# GNNS_SAM-M10Q-00B.net
KiCad netlist of a schematic drawn in Altium Designer
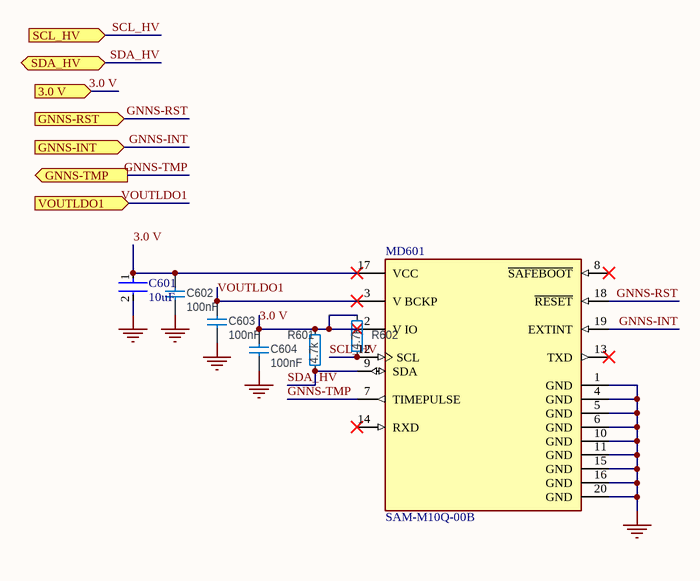
[diagram p0: GNNS (SAM-M10Q-00B).SchDoc]

(export (version "E")
  (design (tool "Eeschema 10.0.6"))
  (components
    (comp (ref "C601")
      (value "10uF")
      (footprint "FP-GRM188-0_2-MFG")
      (description "Chip Multilayer Ceramic Capacitors for General Purpose, 0603, 10uF, X5R, 15%, 20%, 25V")
      (fields (field (name "TOLERANCE") "20%") (field (name "VOLTAGE") "25V"))
      (libsource (lib "Altium Content Vault") (part "11868f565c42a9108669ba33697ecf6"))
    )
    (comp (ref "C602")
      (value "100nF")
      (footprint "CAPC0603X03L_C")
      (description "Capacitor, X7S, ±10%")
      (fields (field (name "AUTHOR") "rsk"))
      (libsource (lib "Watch_Components") (part "C0201-100n-16V-X7S"))
    )
    (comp (ref "C603")
      (value "100nF")
      (footprint "CAPC0603X03L_C")
      (description "Capacitor, X7S, ±10%")
      (fields (field (name "AUTHOR") "rsk"))
      (libsource (lib "Watch_Components") (part "C0201-100n-16V-X7S"))
    )
    (comp (ref "C604")
      (value "100nF")
      (footprint "CAPC0603X03L_C")
      (description "Capacitor, X7S, ±10%")
      (fields (field (name "AUTHOR") "rsk"))
      (libsource (lib "Watch_Components") (part "C0201-100n-16V-X7S"))
    )
    (comp (ref "MD601")
      (value "SAM-M10Q-00B")
      (footprint "FP-SAM-M10Q-00B-MFG")
      (description "M10 GNSS LGA PATCH ANTENNA MOD")
      (libsource (lib "Altium Content Vault") (part "1cb72461910aa5e6ea511d063e6c758"))
    )
    (comp (ref "R601")
      (value "4.7k")
      (footprint "RESC0603X03L_C")
      (description "Resistor, ±1%, 0.05W")
      (fields (field (name "AUTHOR") "rsk"))
      (libsource (lib "Watch_Components") (part "R0201"))
    )
    (comp (ref "R602")
      (value "4.7k")
      (footprint "RESC0603X03L_C")
      (description "Resistor, ±1%, 0.05W")
      (fields (field (name "AUTHOR") "rsk"))
      (libsource (lib "Watch_Components") (part "R0201"))
    )
  )
  (nets
    (net (code "1") (name "/3.0 V") (class "Default")
      (node (ref "C601") (pin "1") (pinfunction "1_1") (pintype "passive"))
      (node (ref "C602") (pin "2") (pinfunction "2_2") (pintype "passive"))
      (node (ref "C604") (pin "2") (pinfunction "2_2") (pintype "passive"))
      (node (ref "MD601") (pin "17") (pinfunction "VCC_17") (pintype "power_in"))
      (node (ref "MD601") (pin "2") (pinfunction "V_IO_2") (pintype "power_in"))
      (node (ref "R601") (pin "1") (pinfunction "1_1") (pintype "passive"))
      (node (ref "R602") (pin "1") (pinfunction "1_1") (pintype "passive"))
    )
    (net (code "2") (name "/GNNS-INT") (class "Default")
      (node (ref "MD601") (pin "19") (pinfunction "EXTINT_19") (pintype "input"))
    )
    (net (code "3") (name "/GNNS-RST") (class "Default")
      (node (ref "MD601") (pin "18") (pinfunction "~{RESET}_18") (pintype "input"))
    )
    (net (code "4") (name "/GNNS-TMP") (class "Default")
      (node (ref "MD601") (pin "7") (pinfunction "TIMEPULSE_7") (pintype "output"))
    )
    (net (code "5") (name "/SCL_HV") (class "Default")
      (node (ref "MD601") (pin "12") (pinfunction "SCL_12") (pintype "input"))
      (node (ref "R602") (pin "2") (pinfunction "2_2") (pintype "passive"))
    )
    (net (code "6") (name "/SDA_HV") (class "Default")
      (node (ref "MD601") (pin "9") (pinfunction "SDA_9") (pintype "bidirectional"))
      (node (ref "R601") (pin "2") (pinfunction "2_2") (pintype "passive"))
    )
    (net (code "7") (name "/VOUTLDO1") (class "Default")
      (node (ref "C603") (pin "2") (pinfunction "2_2") (pintype "passive"))
      (node (ref "MD601") (pin "3") (pinfunction "V_BCKP_3") (pintype "power_in"))
    )
    (net (code "8") (name "GND") (class "Default")
      (node (ref "C601") (pin "2") (pinfunction "2_2") (pintype "passive"))
      (node (ref "C602") (pin "1") (pinfunction "1_1") (pintype "passive"))
      (node (ref "C603") (pin "1") (pinfunction "1_1") (pintype "passive"))
      (node (ref "C604") (pin "1") (pinfunction "1_1") (pintype "passive"))
      (node (ref "MD601") (pin "1") (pinfunction "GND_1") (pintype "power_in"))
      (node (ref "MD601") (pin "10") (pinfunction "GND_10") (pintype "power_in"))
      (node (ref "MD601") (pin "11") (pinfunction "GND_11") (pintype "power_in"))
      (node (ref "MD601") (pin "15") (pinfunction "GND_15") (pintype "power_in"))
      (node (ref "MD601") (pin "16") (pinfunction "GND_16") (pintype "power_in"))
      (node (ref "MD601") (pin "20") (pinfunction "GND_20") (pintype "power_in"))
      (node (ref "MD601") (pin "4") (pinfunction "GND_4") (pintype "power_in"))
      (node (ref "MD601") (pin "5") (pinfunction "GND_5") (pintype "power_in"))
      (node (ref "MD601") (pin "6") (pinfunction "GND_6") (pintype "power_in"))
    )
    (net (code "9") (name "unconnected-(MD601-RXD-Pad14)") (class "Default")
      (node (ref "MD601") (pin "14") (pinfunction "RXD_14") (pintype "input+no_connect"))
    )
    (net (code "10") (name "unconnected-(MD601-TXD-Pad13)") (class "Default")
      (node (ref "MD601") (pin "13") (pinfunction "TXD_13") (pintype "output+no_connect"))
    )
    (net (code "11") (name "unconnected-(MD601-~{SAFEBOOT}-Pad8)") (class "Default")
      (node (ref "MD601") (pin "8") (pinfunction "~{SAFEBOOT}_8") (pintype "input+no_connect"))
    )
  )
)
